# root.net
KiCad netlist of a schematic drawn in Altium Designer
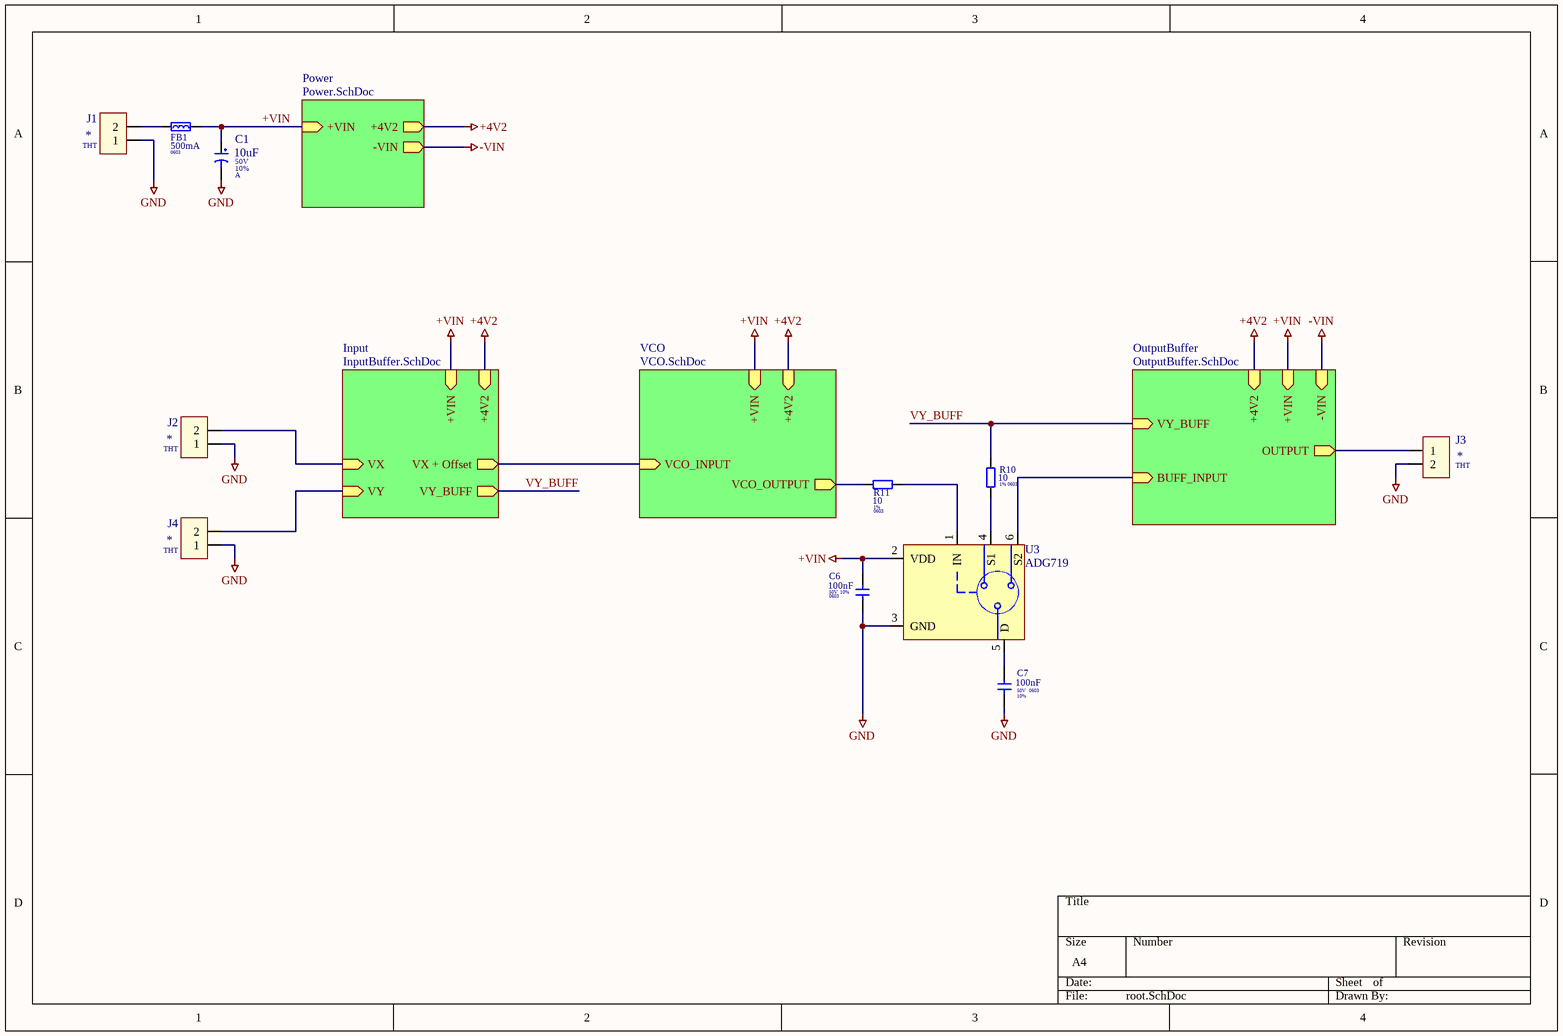
[diagram p0: root.SchDoc]

(export (version "E")
  (design (tool "Eeschema 10.0.6"))
  (components
    (comp (ref "C1")
      (value "10uF")
      (footprint "CAPMP3217X16L")
      (fields
        (field (name "VOLTAGE") "50V")
        (field (name "PACKAGE") "A")
        (field (name "TOLERANT") "10%")
        (field (name "Comment") "10uF/50V")
      )
      (libsource (lib "Falcon-SchMain-Lib") (part "C_TANTAL"))
    )
    (comp (ref "C6")
      (value "100nF")
      (footprint "CAPC1608X06M")
      (fields
        (field (name "VOLTAGE") "50V")
        (field (name "TOLERANT") "10%")
        (field (name "PACKAGE") "0603")
        (field (name "Comment") "100nF/50V")
      )
      (libsource (lib "Falcon-SchMain-Lib") (part "C"))
    )
    (comp (ref "C7")
      (value "100nF")
      (footprint "CAPC1608X06M")
      (fields
        (field (name "VOLTAGE") "50V")
        (field (name "TOLERANT") "10%")
        (field (name "PACKAGE") "0603")
        (field (name "Comment") "100nF/50V")
      )
      (libsource (lib "Falcon-SchMain-Lib") (part "C"))
    )
    (comp (ref "FB1")
      (value "500mA")
      (footprint "INDC2012X07N")
      (fields (field (name "PACKAGE") "0603"))
      (libsource (lib "Falcon-SchMain-Lib") (part "FB"))
    )
    (comp (ref "J1")
      (value "*")
      (footprint "ARK2")
      (fields (field (name "ALTIUM_VALUE") "*") (field (name "PACKAGE") "THT"))
      (libsource (lib "Falcon-SchMain-Lib") (part "CON_2PIN"))
    )
    (comp (ref "J2")
      (value "*")
      (footprint "ARK2")
      (fields (field (name "ALTIUM_VALUE") "*") (field (name "PACKAGE") "THT"))
      (libsource (lib "Falcon-SchMain-Lib") (part "CON_2PIN"))
    )
    (comp (ref "J3")
      (value "*")
      (footprint "ARK2")
      (fields (field (name "ALTIUM_VALUE") "*") (field (name "PACKAGE") "THT"))
      (libsource (lib "") (part "CON_2PIN_1"))
    )
    (comp (ref "J4")
      (value "*")
      (footprint "ARK2")
      (fields (field (name "ALTIUM_VALUE") "*") (field (name "PACKAGE") "THT"))
      (libsource (lib "Falcon-SchMain-Lib") (part "CON_2PIN"))
    )
    (comp (ref "R10")
      (value "10")
      (footprint "RESC1608X06L")
      (fields
        (field (name "PACKAGE") "0603")
        (field (name "TOLERANCE") "1%")
        (field (name "Comment") "10 1%")
      )
      (libsource (lib "") (part "R_1"))
    )
    (comp (ref "R11")
      (value "10")
      (footprint "RESC1608X06L")
      (fields
        (field (name "PACKAGE") "0603")
        (field (name "TOLERANCE") "1%")
        (field (name "Comment") "10 1%")
      )
      (libsource (lib "Falcon-SchMain-Lib") (part "R"))
    )
    (comp (ref "U3")
      (value "ADG719")
      (footprint "SOT363/SC-88")
      (description "Analogue Switch ICs LOW VOLTAGE SINGEL SPDT")
      (libsource (lib "Falcon-SchMain-Lib") (part "ADG719"))
    )
  )
  (nets
    (net (code "2") (name "+VIN") (class "Default")
      (node (ref "C1") (pin "1") (pinfunction "1_1") (pintype "passive"))
      (node (ref "C6") (pin "2") (pinfunction "2_2") (pintype "passive"))
      (node (ref "FB1") (pin "2") (pinfunction "2_2") (pintype "passive"))
      (node (ref "U3") (pin "2") (pinfunction "VDD_2") (pintype "power_in"))
    )
    (net (code "4") (name "/BUFF_INPUT") (class "Default")
      (node (ref "U3") (pin "6") (pinfunction "S2_6") (pintype "power_in"))
    )
    (net (code "5") (name "/OUTPUT") (class "Default")
      (node (ref "J3") (pin "1") (pinfunction "1_1") (pintype "passive"))
    )
    (net (code "6") (name "/VCO_OUTPUT") (class "Default")
      (node (ref "R11") (pin "1") (pinfunction "1_1") (pintype "passive"))
    )
    (net (code "7") (name "/VX") (class "Default")
      (node (ref "J2") (pin "2") (pinfunction "2_2") (pintype "passive"))
    )
    (net (code "9") (name "/VY") (class "Default")
      (node (ref "J4") (pin "2") (pinfunction "2_2") (pintype "passive"))
    )
    (net (code "10") (name "/VY_BUFF") (class "Default")
      (node (ref "R10") (pin "2") (pinfunction "2_2") (pintype "passive"))
    )
    (net (code "11") (name "GND") (class "Default")
      (node (ref "C1") (pin "2") (pinfunction "2_2") (pintype "passive"))
      (node (ref "C6") (pin "1") (pinfunction "1_1") (pintype "passive"))
      (node (ref "C7") (pin "1") (pinfunction "1_1") (pintype "passive"))
      (node (ref "J1") (pin "1") (pinfunction "1_1") (pintype "passive"))
      (node (ref "J2") (pin "1") (pinfunction "1_1") (pintype "passive"))
      (node (ref "J3") (pin "2") (pinfunction "2_2") (pintype "passive"))
      (node (ref "J4") (pin "1") (pinfunction "1_1") (pintype "passive"))
      (node (ref "U3") (pin "3") (pinfunction "GND_3") (pintype "power_in"))
    )
    (net (code "12") (name "Net-(FB1-Pad1)") (class "Default")
      (node (ref "FB1") (pin "1") (pinfunction "1_1") (pintype "passive"))
      (node (ref "J1") (pin "2") (pinfunction "2_2") (pintype "passive"))
    )
    (net (code "13") (name "Net-(U3-D)") (class "Default")
      (node (ref "C7") (pin "2") (pinfunction "2_2") (pintype "passive"))
      (node (ref "U3") (pin "5") (pinfunction "D_5") (pintype "power_in"))
    )
    (net (code "14") (name "Net-(U3-IN)") (class "Default")
      (node (ref "R11") (pin "2") (pinfunction "2_2") (pintype "passive"))
      (node (ref "U3") (pin "1") (pinfunction "IN_1") (pintype "power_in"))
    )
    (net (code "15") (name "Net-(U3-S1)") (class "Default")
      (node (ref "R10") (pin "1") (pinfunction "1_1") (pintype "passive"))
      (node (ref "U3") (pin "4") (pinfunction "S1_4") (pintype "power_in"))
    )
  )
)
